# tj208_EL311.net
KiCad netlist of a schematic drawn in EAGLE
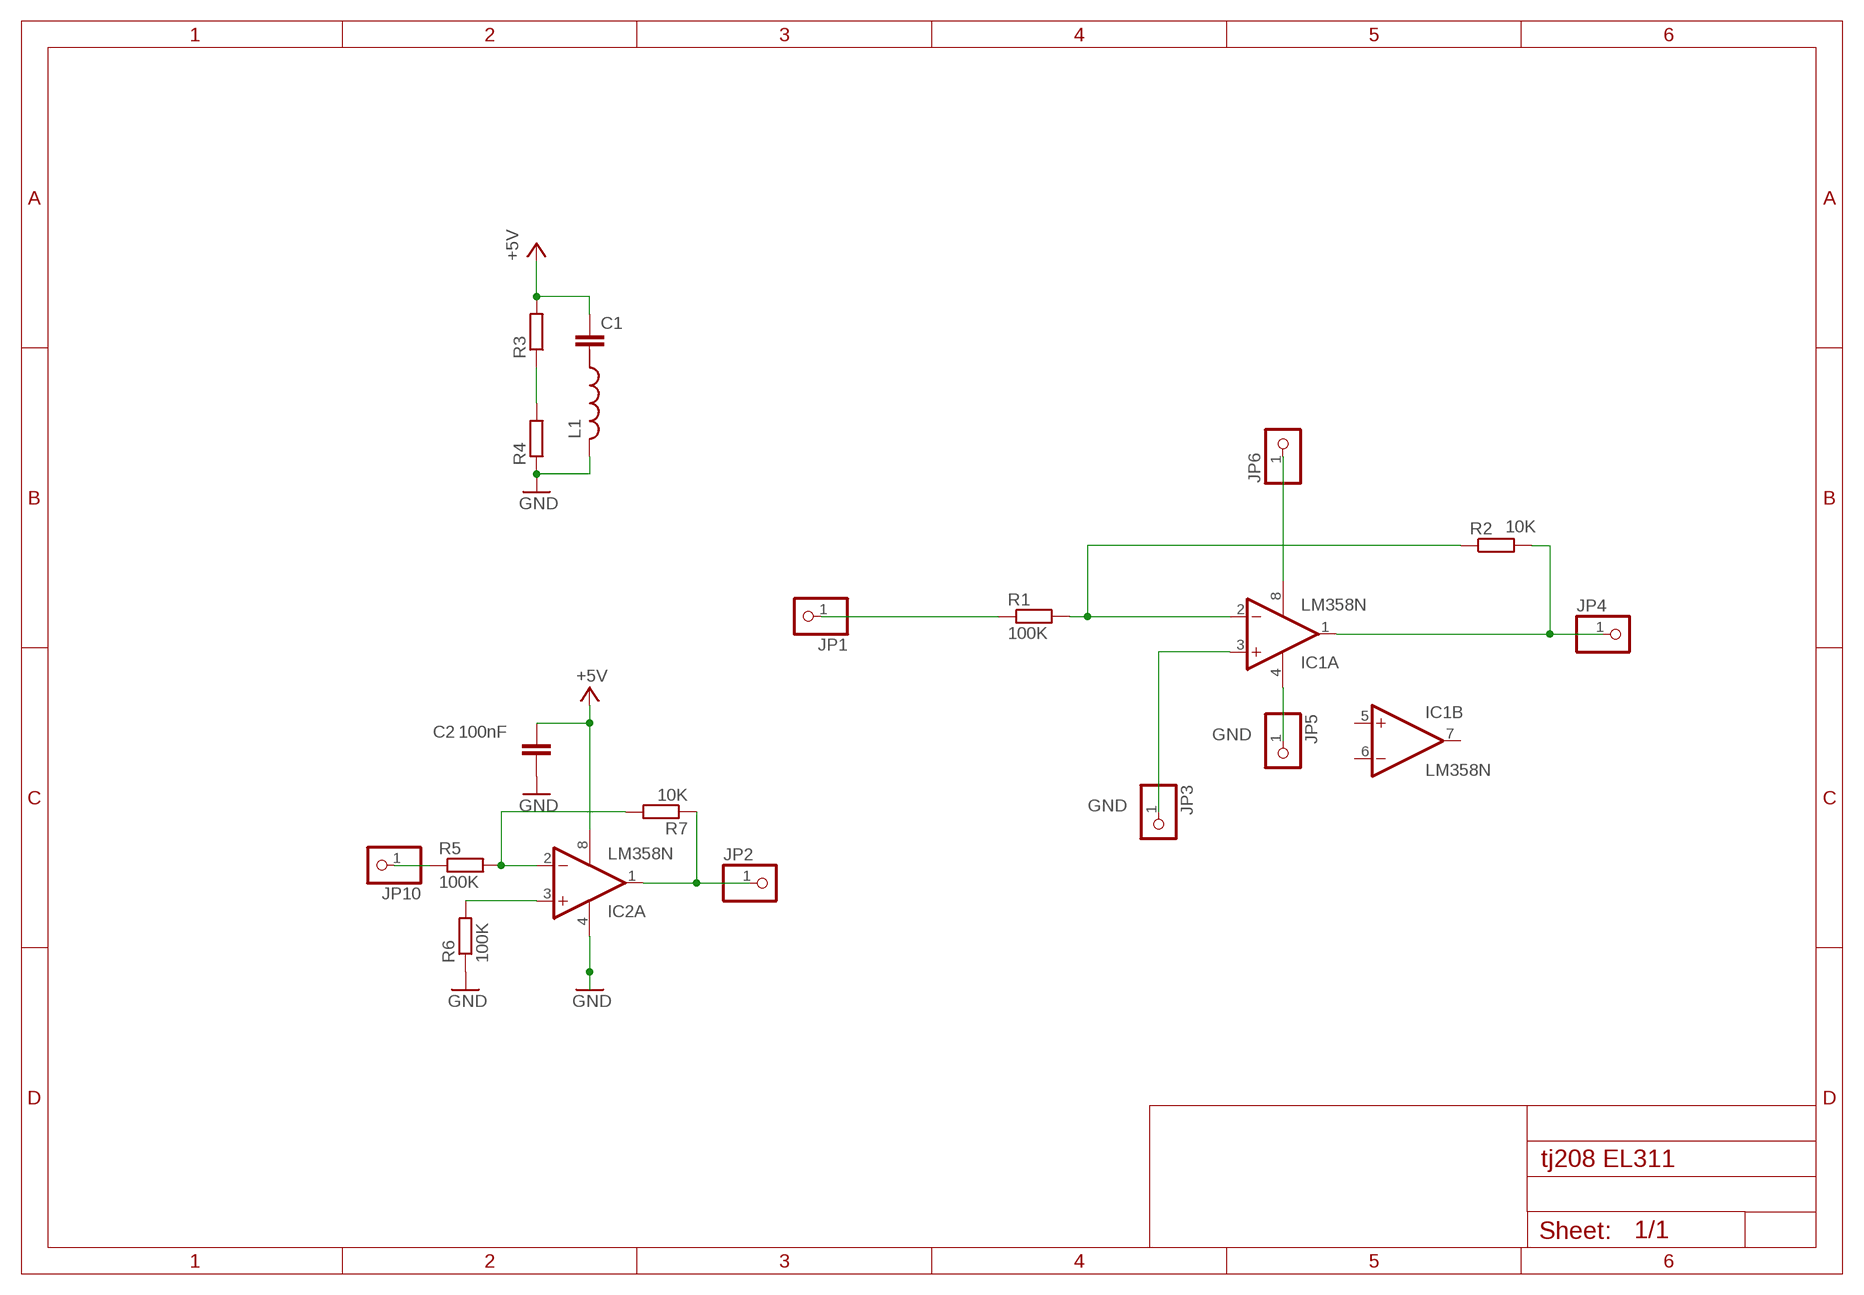
[diagram p0: schematic, sheet 1]

(export (version "E")
  (design (tool "Eeschema 10.0.6"))
  (components
    (comp (ref "C1")
      (value "C-EU025-024X044")
      (footprint "eagle-import:C025-024X044")
      (libsource (lib "eagle-import") (part "C-EU025-024X044"))
    )
    (comp (ref "C2")
      (value "100nF")
      (footprint "eagle-import:C025-024X044")
      (libsource (lib "eagle-import") (part "C-EU025-024X044"))
    )
    (comp (ref "IC1")
      (value "LM358N")
      (footprint "eagle-import:DIL08")
      (libsource (lib "eagle-import") (part "LM358N"))
    )
    (comp (ref "IC2")
      (value "LM358N")
      (footprint "eagle-import:DIL08")
      (libsource (lib "eagle-import") (part "LM358N"))
    )
    (comp (ref "JP1")
      (value "PINHD-1X1")
      (footprint "eagle-import:1X01")
      (libsource (lib "eagle-import") (part "PINHD-1X1"))
    )
    (comp (ref "JP2")
      (value "PINHD-1X1")
      (footprint "eagle-import:1X01")
      (libsource (lib "eagle-import") (part "PINHD-1X1"))
    )
    (comp (ref "JP3")
      (value "PINHD-1X1")
      (footprint "eagle-import:1X01")
      (libsource (lib "eagle-import") (part "PINHD-1X1"))
    )
    (comp (ref "JP4")
      (value "PINHD-1X1")
      (footprint "eagle-import:1X01")
      (libsource (lib "eagle-import") (part "PINHD-1X1"))
    )
    (comp (ref "JP5")
      (value "PINHD-1X1")
      (footprint "eagle-import:1X01")
      (libsource (lib "eagle-import") (part "PINHD-1X1"))
    )
    (comp (ref "JP6")
      (value "PINHD-1X1")
      (footprint "eagle-import:1X01")
      (libsource (lib "eagle-import") (part "PINHD-1X1"))
    )
    (comp (ref "JP10")
      (value "PINHD-1X1")
      (footprint "eagle-import:1X01")
      (libsource (lib "eagle-import") (part "PINHD-1X1"))
    )
    (comp (ref "L1")
      (value "L-US0204/5")
      (footprint "eagle-import:0204_5")
      (libsource (lib "eagle-import") (part "L-US0204/5"))
    )
    (comp (ref "R1")
      (value "100K")
      (footprint "eagle-import:0207_10")
      (libsource (lib "eagle-import") (part "R-EU_0207/10"))
    )
    (comp (ref "R2")
      (value "10K")
      (footprint "eagle-import:0207_10")
      (libsource (lib "eagle-import") (part "R-EU_0207/10"))
    )
    (comp (ref "R3")
      (value "R-EU_0207/5V")
      (footprint "eagle-import:0207_5V")
      (libsource (lib "eagle-import") (part "R-EU_0207/5V"))
    )
    (comp (ref "R4")
      (value "R-EU_0207/5V")
      (footprint "eagle-import:0207_5V")
      (libsource (lib "eagle-import") (part "R-EU_0207/5V"))
    )
    (comp (ref "R5")
      (value "100K")
      (footprint "eagle-import:0207_10")
      (libsource (lib "eagle-import") (part "R-EU_0207/10"))
    )
    (comp (ref "R6")
      (value "100K")
      (footprint "eagle-import:0207_5V")
      (libsource (lib "eagle-import") (part "R-EU_0207/5V"))
    )
    (comp (ref "R7")
      (value "10K")
      (footprint "eagle-import:0207_5V")
      (libsource (lib "eagle-import") (part "R-EU_0207/5V"))
    )
  )
  (nets
    (net (code "1") (name "+5V") (class "Default")
      (node (ref "C1") (pin "1") (pinfunction "1_1") (pintype "passive"))
      (node (ref "C2") (pin "1") (pinfunction "1_1") (pintype "passive"))
      (node (ref "IC2") (pin "8") (pinfunction "V+_8") (pintype "power_in"))
      (node (ref "R3") (pin "2") (pinfunction "2_2") (pintype "passive"))
    )
    (net (code "2") (name "GND") (class "Default")
      (node (ref "C2") (pin "2") (pinfunction "2_2") (pintype "passive"))
      (node (ref "IC1") (pin "3") (pinfunction "+IN_3") (pintype "input"))
      (node (ref "IC1") (pin "4") (pinfunction "V-_4") (pintype "power_in"))
      (node (ref "IC2") (pin "3") (pinfunction "+IN_3") (pintype "input"))
      (node (ref "IC2") (pin "4") (pinfunction "V-_4") (pintype "power_in"))
      (node (ref "JP3") (pin "1") (pinfunction "1_1") (pintype "passive"))
      (node (ref "JP5") (pin "1") (pinfunction "1_1") (pintype "passive"))
      (node (ref "L1") (pin "2") (pinfunction "2_2") (pintype "passive"))
      (node (ref "R4") (pin "1") (pinfunction "1_1") (pintype "passive"))
      (node (ref "R6") (pin "1") (pinfunction "1_1") (pintype "passive"))
      (node (ref "R6") (pin "2") (pinfunction "2_2") (pintype "passive"))
    )
    (net (code "3") (name "Net-(IC1A--IN)") (class "Default")
      (node (ref "IC1") (pin "2") (pinfunction "-IN_2") (pintype "input"))
      (node (ref "R1") (pin "2") (pinfunction "2_2") (pintype "passive"))
      (node (ref "R2") (pin "1") (pinfunction "1_1") (pintype "passive"))
    )
    (net (code "4") (name "Net-(IC1A-OUT)") (class "Default")
      (node (ref "IC1") (pin "1") (pinfunction "OUT_1") (pintype "output"))
      (node (ref "JP4") (pin "1") (pinfunction "1_1") (pintype "passive"))
      (node (ref "R2") (pin "2") (pinfunction "2_2") (pintype "passive"))
    )
    (net (code "5") (name "Net-(IC1C-V+)") (class "Default")
      (node (ref "IC1") (pin "8") (pinfunction "V+_8") (pintype "power_in"))
      (node (ref "JP6") (pin "1") (pinfunction "1_1") (pintype "passive"))
    )
    (net (code "6") (name "Net-(IC2A--IN)") (class "Default")
      (node (ref "IC2") (pin "2") (pinfunction "-IN_2") (pintype "input"))
      (node (ref "R5") (pin "2") (pinfunction "2_2") (pintype "passive"))
      (node (ref "R7") (pin "2") (pinfunction "2_2") (pintype "passive"))
    )
    (net (code "7") (name "Net-(IC2A-OUT)") (class "Default")
      (node (ref "IC2") (pin "1") (pinfunction "OUT_1") (pintype "output"))
      (node (ref "JP2") (pin "1") (pinfunction "1_1") (pintype "passive"))
      (node (ref "R7") (pin "1") (pinfunction "1_1") (pintype "passive"))
    )
    (net (code "8") (name "Net-(JP1-Pad1)") (class "Default")
      (node (ref "JP1") (pin "1") (pinfunction "1_1") (pintype "passive"))
      (node (ref "R1") (pin "1") (pinfunction "1_1") (pintype "passive"))
    )
    (net (code "9") (name "Net-(JP10-Pad1)") (class "Default")
      (node (ref "JP10") (pin "1") (pinfunction "1_1") (pintype "passive"))
      (node (ref "R5") (pin "1") (pinfunction "1_1") (pintype "passive"))
    )
    (net (code "10") (name "Net-(R3-Pad1)") (class "Default")
      (node (ref "R3") (pin "1") (pinfunction "1_1") (pintype "passive"))
      (node (ref "R4") (pin "2") (pinfunction "2_2") (pintype "passive"))
    )
    (net (code "11") (name "unconnected-(C1-Pad2)") (class "Default")
      (node (ref "C1") (pin "2") (pinfunction "2_2") (pintype "passive"))
    )
    (net (code "12") (name "unconnected-(IC1B-+IN-Pad5)") (class "Default")
      (node (ref "IC1") (pin "5") (pinfunction "+IN_5") (pintype "input"))
    )
    (net (code "13") (name "unconnected-(IC1B--IN-Pad6)") (class "Default")
      (node (ref "IC1") (pin "6") (pinfunction "-IN_6") (pintype "input"))
    )
    (net (code "14") (name "unconnected-(IC1B-OUT-Pad7)") (class "Default")
      (node (ref "IC1") (pin "7") (pinfunction "OUT_7") (pintype "output"))
    )
    (net (code "15") (name "unconnected-(L1-Pad1)") (class "Default")
      (node (ref "L1") (pin "1") (pinfunction "1_1") (pintype "passive"))
    )
  )
)
